# Schemactic_LEDspot.net
KiCad netlist of a schematic drawn in EasyEDA
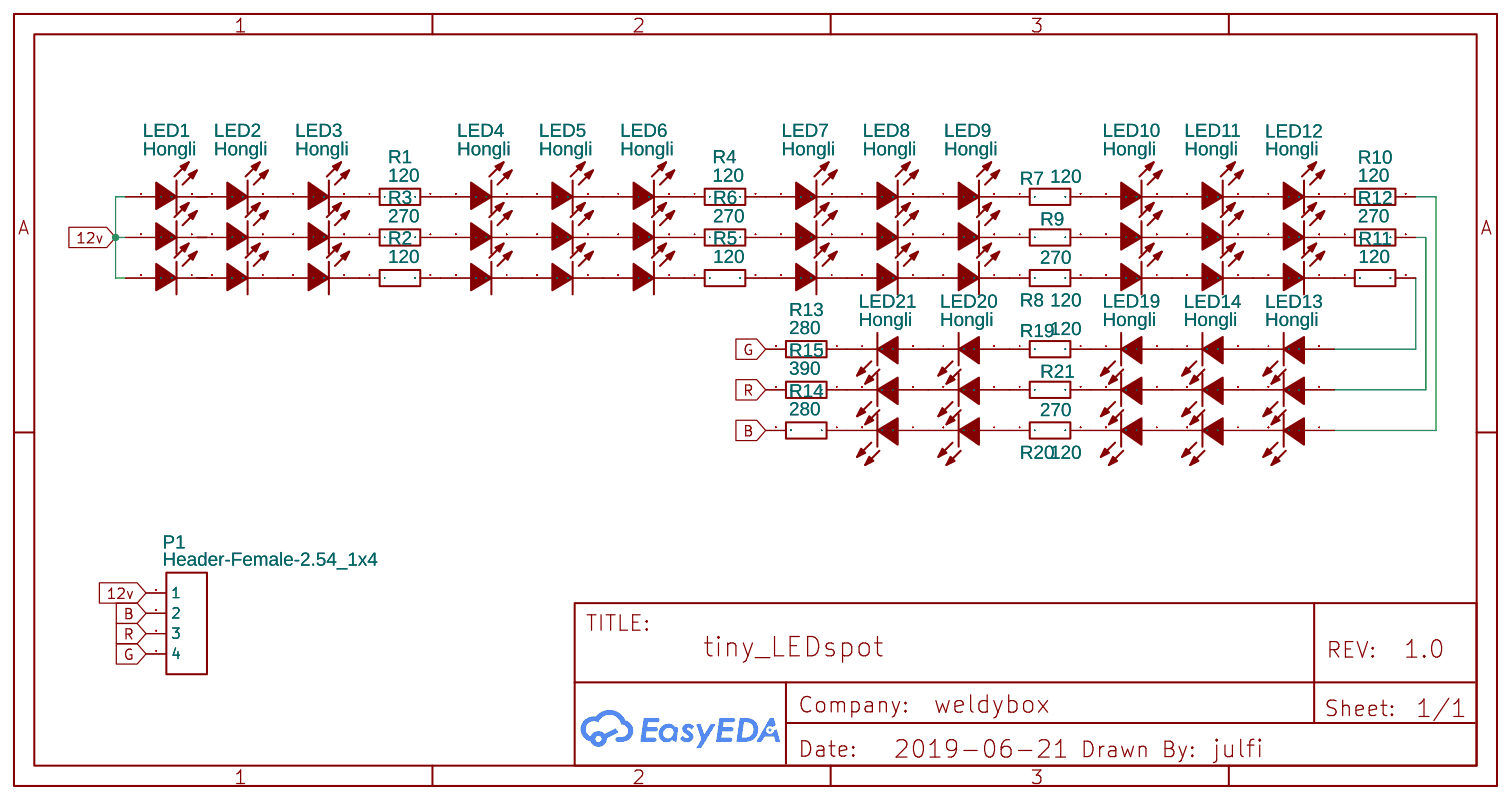
[diagram p0: schematic sheet]

(export (version "E")
  (design (tool "Eeschema 10.0.6"))
  (components
    (comp (ref "LED1")
      (value "Hongli")
      (fields
        (field (name "BOM_Manufacturer Part") "HL-AF-5060H271BU46FU79GC-S1-THL")
        (field (name "BOM_Supplier Part") "C219409")
      )
      (libsource (lib "") (part "Unknown_70_440"))
    )
    (comp (ref "LED2")
      (value "Hongli")
      (fields
        (field (name "BOM_Manufacturer Part") "HL-AF-5060H271BU46FU79GC-S1-THL")
        (field (name "BOM_Supplier Part") "C219409")
      )
      (libsource (lib "") (part "Unknown_105_440"))
    )
    (comp (ref "LED3")
      (value "Hongli")
      (fields
        (field (name "BOM_Manufacturer Part") "HL-AF-5060H271BU46FU79GC-S1-THL")
        (field (name "BOM_Supplier Part") "C219409")
      )
      (libsource (lib "") (part "Unknown_145_440"))
    )
    (comp (ref "LED4")
      (value "Hongli")
      (fields
        (field (name "BOM_Manufacturer Part") "HL-AF-5060H271BU46FU79GC-S1-THL")
        (field (name "BOM_Supplier Part") "C219409")
      )
      (libsource (lib "") (part "Unknown_225_440"))
    )
    (comp (ref "LED5")
      (value "Hongli")
      (fields
        (field (name "BOM_Manufacturer Part") "HL-AF-5060H271BU46FU79GC-S1-THL")
        (field (name "BOM_Supplier Part") "C219409")
      )
      (libsource (lib "") (part "Unknown_265_440"))
    )
    (comp (ref "LED6")
      (value "Hongli")
      (fields
        (field (name "BOM_Manufacturer Part") "HL-AF-5060H271BU46FU79GC-S1-THL")
        (field (name "BOM_Supplier Part") "C219409")
      )
      (libsource (lib "") (part "Unknown_305_440"))
    )
    (comp (ref "LED7")
      (value "Hongli")
      (fields
        (field (name "BOM_Manufacturer Part") "HL-AF-5060H271BU46FU79GC-S1-THL")
        (field (name "BOM_Supplier Part") "C219409")
      )
      (libsource (lib "") (part "Unknown_385_440"))
    )
    (comp (ref "LED8")
      (value "Hongli")
      (fields
        (field (name "BOM_Manufacturer Part") "HL-AF-5060H271BU46FU79GC-S1-THL")
        (field (name "BOM_Supplier Part") "C219409")
      )
      (libsource (lib "") (part "Unknown_425_440"))
    )
    (comp (ref "LED9")
      (value "Hongli")
      (fields
        (field (name "BOM_Manufacturer Part") "HL-AF-5060H271BU46FU79GC-S1-THL")
        (field (name "BOM_Supplier Part") "C219409")
      )
      (libsource (lib "") (part "Unknown_465_440"))
    )
    (comp (ref "LED10")
      (value "Hongli")
      (fields
        (field (name "BOM_Manufacturer Part") "HL-AF-5060H271BU46FU79GC-S1-THL")
        (field (name "BOM_Supplier Part") "C219409")
      )
      (libsource (lib "") (part "Unknown_545_440"))
    )
    (comp (ref "LED11")
      (value "Hongli")
      (fields
        (field (name "BOM_Manufacturer Part") "HL-AF-5060H271BU46FU79GC-S1-THL")
        (field (name "BOM_Supplier Part") "C219409")
      )
      (libsource (lib "") (part "Unknown_585_440"))
    )
    (comp (ref "LED12")
      (value "Hongli")
      (fields
        (field (name "BOM_Manufacturer Part") "HL-AF-5060H271BU46FU79GC-S1-THL")
        (field (name "BOM_Supplier Part") "C219409")
      )
      (libsource (lib "") (part "Unknown_625_440"))
    )
    (comp (ref "LED13")
      (value "Hongli")
      (fields
        (field (name "BOM_Manufacturer Part") "HL-AF-5060H271BU46FU79GC-S1-THL")
        (field (name "BOM_Supplier Part") "C219409")
      )
      (libsource (lib "") (part "Unknown_625_515"))
    )
    (comp (ref "LED14")
      (value "Hongli")
      (fields
        (field (name "BOM_Manufacturer Part") "HL-AF-5060H271BU46FU79GC-S1-THL")
        (field (name "BOM_Supplier Part") "C219409")
      )
      (libsource (lib "") (part "Unknown_585_515"))
    )
    (comp (ref "LED19")
      (value "Hongli")
      (fields
        (field (name "BOM_Manufacturer Part") "HL-AF-5060H271BU46FU79GC-S1-THL")
        (field (name "BOM_Supplier Part") "C219409")
      )
      (libsource (lib "") (part "Unknown_545_515"))
    )
    (comp (ref "LED20")
      (value "Hongli")
      (fields
        (field (name "BOM_Manufacturer Part") "HL-AF-5060H271BU46FU79GC-S1-THL")
        (field (name "BOM_Supplier Part") "C219409")
      )
      (libsource (lib "") (part "Unknown_465_515"))
    )
    (comp (ref "LED21")
      (value "Hongli")
      (fields
        (field (name "BOM_Manufacturer Part") "HL-AF-5060H271BU46FU79GC-S1-THL")
        (field (name "BOM_Supplier Part") "C219409")
      )
      (libsource (lib "") (part "Unknown_425_515"))
    )
    (comp (ref "P1")
      (value "Header-Female-2.54_1x4")
      (fields (field (name "BOM_Supplier Part") "C124413"))
      (libsource (lib "") (part "Unknown_75_630"))
    )
    (comp (ref "R1")
      (value "120")
      (fields
        (field (name "BOM_Manufacturer Part") "0805W8J0121T5E")
        (field (name "BOM_Supplier Part") "C25280")
      )
      (libsource (lib "") (part "0805W8J0121T5E"))
    )
    (comp (ref "R2")
      (value "120")
      (fields
        (field (name "BOM_Manufacturer Part") "0805W8J0121T5E")
        (field (name "BOM_Supplier Part") "C25280")
      )
      (libsource (lib "") (part "0805W8J0121T5E"))
    )
    (comp (ref "R3")
      (value "270")
      (fields
        (field (name "BOM_Manufacturer Part") "RS-05K271JT")
        (field (name "BOM_Supplier Part") "C115004")
      )
      (libsource (lib "") (part "RS-05K271JT"))
    )
    (comp (ref "R4")
      (value "120")
      (fields
        (field (name "BOM_Manufacturer Part") "0805W8J0121T5E")
        (field (name "BOM_Supplier Part") "C25280")
      )
      (libsource (lib "") (part "0805W8J0121T5E"))
    )
    (comp (ref "R5")
      (value "120")
      (fields
        (field (name "BOM_Manufacturer Part") "0805W8J0121T5E")
        (field (name "BOM_Supplier Part") "C25280")
      )
      (libsource (lib "") (part "0805W8J0121T5E"))
    )
    (comp (ref "R6")
      (value "270")
      (fields
        (field (name "BOM_Manufacturer Part") "RS-05K271JT")
        (field (name "BOM_Supplier Part") "C115004")
      )
      (libsource (lib "") (part "RS-05K271JT"))
    )
    (comp (ref "R7")
      (value "120")
      (fields
        (field (name "BOM_Manufacturer Part") "0805W8J0121T5E")
        (field (name "BOM_Supplier Part") "C25280")
      )
      (libsource (lib "") (part "0805W8J0121T5E"))
    )
    (comp (ref "R8")
      (value "120")
      (fields
        (field (name "BOM_Manufacturer Part") "0805W8J0121T5E")
        (field (name "BOM_Supplier Part") "C25280")
      )
      (libsource (lib "") (part "0805W8J0121T5E"))
    )
    (comp (ref "R9")
      (value "270")
      (fields
        (field (name "BOM_Manufacturer Part") "RS-05K271JT")
        (field (name "BOM_Supplier Part") "C115004")
      )
      (libsource (lib "") (part "RS-05K271JT"))
    )
    (comp (ref "R10")
      (value "120")
      (fields
        (field (name "BOM_Manufacturer Part") "0805W8J0121T5E")
        (field (name "BOM_Supplier Part") "C25280")
      )
      (libsource (lib "") (part "0805W8J0121T5E"))
    )
    (comp (ref "R11")
      (value "120")
      (fields
        (field (name "BOM_Manufacturer Part") "0805W8J0121T5E")
        (field (name "BOM_Supplier Part") "C25280")
      )
      (libsource (lib "") (part "0805W8J0121T5E"))
    )
    (comp (ref "R12")
      (value "270")
      (fields
        (field (name "BOM_Manufacturer Part") "RS-05K271JT")
        (field (name "BOM_Supplier Part") "C115004")
      )
      (libsource (lib "") (part "RS-05K271JT"))
    )
    (comp (ref "R13")
      (value "280")
      (fields
        (field (name "BOM_Manufacturer Part") "0805W8F2800T5E")
        (field (name "BOM_Supplier Part") "C247037")
      )
      (libsource (lib "") (part "0805W8F2800T5E"))
    )
    (comp (ref "R14")
      (value "280")
      (fields
        (field (name "BOM_Manufacturer Part") "0805W8F2800T5E")
        (field (name "BOM_Supplier Part") "C247037")
      )
      (libsource (lib "") (part "0805W8F2800T5E"))
    )
    (comp (ref "R15")
      (value "390")
      (fields
        (field (name "BOM_Manufacturer Part") "RTT053900FTP")
        (field (name "BOM_Supplier Part") "C104278")
      )
      (libsource (lib "") (part "RTT053900FTP"))
    )
    (comp (ref "R19")
      (value "120")
      (fields
        (field (name "BOM_Manufacturer Part") "0805W8J0121T5E")
        (field (name "BOM_Supplier Part") "C25280")
      )
      (libsource (lib "") (part "0805W8J0121T5E"))
    )
    (comp (ref "R20")
      (value "120")
      (fields
        (field (name "BOM_Manufacturer Part") "0805W8J0121T5E")
        (field (name "BOM_Supplier Part") "C25280")
      )
      (libsource (lib "") (part "0805W8J0121T5E"))
    )
    (comp (ref "R21")
      (value "270")
      (fields
        (field (name "BOM_Manufacturer Part") "RS-05K271JT")
        (field (name "BOM_Supplier Part") "C115004")
      )
      (libsource (lib "") (part "RS-05K271JT"))
    )
  )
  (nets
    (net (code "1") (name "12v") (class "Default")
      (node (ref "LED1") (pin "1") (pinfunction "A_1") (pintype "unspecified"))
      (node (ref "LED1") (pin "2") (pinfunction "A_2") (pintype "unspecified"))
      (node (ref "LED1") (pin "3") (pinfunction "A_3") (pintype "unspecified"))
      (node (ref "P1") (pin "1") (pinfunction "1_1") (pintype "input"))
    )
    (net (code "2") (name "B") (class "Default")
      (node (ref "P1") (pin "2") (pinfunction "2_2") (pintype "input"))
      (node (ref "R14") (pin "2") (pinfunction "2_2") (pintype "unspecified"))
    )
    (net (code "3") (name "G") (class "Default")
      (node (ref "P1") (pin "4") (pinfunction "4_4") (pintype "input"))
      (node (ref "R13") (pin "2") (pinfunction "2_2") (pintype "unspecified"))
    )
    (net (code "4") (name "Net-(LED1-C-Pad4)") (class "Default")
      (node (ref "LED1") (pin "4") (pinfunction "C_4") (pintype "unspecified"))
      (node (ref "LED2") (pin "3") (pinfunction "A_3") (pintype "unspecified"))
    )
    (net (code "5") (name "Net-(LED1-C-Pad5)") (class "Default")
      (node (ref "LED1") (pin "5") (pinfunction "C_5") (pintype "unspecified"))
      (node (ref "LED2") (pin "2") (pinfunction "A_2") (pintype "unspecified"))
    )
    (net (code "6") (name "Net-(LED1-C-Pad6)") (class "Default")
      (node (ref "LED1") (pin "6") (pinfunction "C_6") (pintype "unspecified"))
      (node (ref "LED2") (pin "1") (pinfunction "A_1") (pintype "unspecified"))
    )
    (net (code "7") (name "Net-(LED2-C-Pad4)") (class "Default")
      (node (ref "LED2") (pin "4") (pinfunction "C_4") (pintype "unspecified"))
      (node (ref "LED3") (pin "3") (pinfunction "A_3") (pintype "unspecified"))
    )
    (net (code "8") (name "Net-(LED2-C-Pad5)") (class "Default")
      (node (ref "LED2") (pin "5") (pinfunction "C_5") (pintype "unspecified"))
      (node (ref "LED3") (pin "2") (pinfunction "A_2") (pintype "unspecified"))
    )
    (net (code "9") (name "Net-(LED2-C-Pad6)") (class "Default")
      (node (ref "LED2") (pin "6") (pinfunction "C_6") (pintype "unspecified"))
      (node (ref "LED3") (pin "1") (pinfunction "A_1") (pintype "unspecified"))
    )
    (net (code "10") (name "Net-(LED3-C-Pad4)") (class "Default")
      (node (ref "LED3") (pin "4") (pinfunction "C_4") (pintype "unspecified"))
      (node (ref "R2") (pin "1") (pinfunction "1_1") (pintype "input"))
    )
    (net (code "11") (name "Net-(LED3-C-Pad5)") (class "Default")
      (node (ref "LED3") (pin "5") (pinfunction "C_5") (pintype "unspecified"))
      (node (ref "R3") (pin "1") (pinfunction "1_1") (pintype "input"))
    )
    (net (code "12") (name "Net-(LED3-C-Pad6)") (class "Default")
      (node (ref "LED3") (pin "6") (pinfunction "C_6") (pintype "unspecified"))
      (node (ref "R1") (pin "1") (pinfunction "1_1") (pintype "input"))
    )
    (net (code "13") (name "Net-(LED4-A-Pad1)") (class "Default")
      (node (ref "LED4") (pin "1") (pinfunction "A_1") (pintype "unspecified"))
      (node (ref "R1") (pin "2") (pinfunction "2_2") (pintype "input"))
    )
    (net (code "14") (name "Net-(LED4-A-Pad2)") (class "Default")
      (node (ref "LED4") (pin "2") (pinfunction "A_2") (pintype "unspecified"))
      (node (ref "R3") (pin "2") (pinfunction "2_2") (pintype "input"))
    )
    (net (code "15") (name "Net-(LED4-A-Pad3)") (class "Default")
      (node (ref "LED4") (pin "3") (pinfunction "A_3") (pintype "unspecified"))
      (node (ref "R2") (pin "2") (pinfunction "2_2") (pintype "input"))
    )
    (net (code "16") (name "Net-(LED4-C-Pad4)") (class "Default")
      (node (ref "LED4") (pin "4") (pinfunction "C_4") (pintype "unspecified"))
      (node (ref "LED5") (pin "3") (pinfunction "A_3") (pintype "unspecified"))
    )
    (net (code "17") (name "Net-(LED4-C-Pad5)") (class "Default")
      (node (ref "LED4") (pin "5") (pinfunction "C_5") (pintype "unspecified"))
      (node (ref "LED5") (pin "2") (pinfunction "A_2") (pintype "unspecified"))
    )
    (net (code "18") (name "Net-(LED4-C-Pad6)") (class "Default")
      (node (ref "LED4") (pin "6") (pinfunction "C_6") (pintype "unspecified"))
      (node (ref "LED5") (pin "1") (pinfunction "A_1") (pintype "unspecified"))
    )
    (net (code "19") (name "Net-(LED5-C-Pad4)") (class "Default")
      (node (ref "LED5") (pin "4") (pinfunction "C_4") (pintype "unspecified"))
      (node (ref "LED6") (pin "3") (pinfunction "A_3") (pintype "unspecified"))
    )
    (net (code "20") (name "Net-(LED5-C-Pad5)") (class "Default")
      (node (ref "LED5") (pin "5") (pinfunction "C_5") (pintype "unspecified"))
      (node (ref "LED6") (pin "2") (pinfunction "A_2") (pintype "unspecified"))
    )
    (net (code "21") (name "Net-(LED5-C-Pad6)") (class "Default")
      (node (ref "LED5") (pin "6") (pinfunction "C_6") (pintype "unspecified"))
      (node (ref "LED6") (pin "1") (pinfunction "A_1") (pintype "unspecified"))
    )
    (net (code "22") (name "Net-(LED6-C-Pad4)") (class "Default")
      (node (ref "LED6") (pin "4") (pinfunction "C_4") (pintype "unspecified"))
      (node (ref "R5") (pin "1") (pinfunction "1_1") (pintype "input"))
    )
    (net (code "23") (name "Net-(LED6-C-Pad5)") (class "Default")
      (node (ref "LED6") (pin "5") (pinfunction "C_5") (pintype "unspecified"))
      (node (ref "R6") (pin "1") (pinfunction "1_1") (pintype "input"))
    )
    (net (code "24") (name "Net-(LED6-C-Pad6)") (class "Default")
      (node (ref "LED6") (pin "6") (pinfunction "C_6") (pintype "unspecified"))
      (node (ref "R4") (pin "1") (pinfunction "1_1") (pintype "input"))
    )
    (net (code "25") (name "Net-(LED7-A-Pad1)") (class "Default")
      (node (ref "LED7") (pin "1") (pinfunction "A_1") (pintype "unspecified"))
      (node (ref "R4") (pin "2") (pinfunction "2_2") (pintype "input"))
    )
    (net (code "26") (name "Net-(LED7-A-Pad2)") (class "Default")
      (node (ref "LED7") (pin "2") (pinfunction "A_2") (pintype "unspecified"))
      (node (ref "R6") (pin "2") (pinfunction "2_2") (pintype "input"))
    )
    (net (code "27") (name "Net-(LED7-A-Pad3)") (class "Default")
      (node (ref "LED7") (pin "3") (pinfunction "A_3") (pintype "unspecified"))
      (node (ref "R5") (pin "2") (pinfunction "2_2") (pintype "input"))
    )
    (net (code "28") (name "Net-(LED7-C-Pad4)") (class "Default")
      (node (ref "LED7") (pin "4") (pinfunction "C_4") (pintype "unspecified"))
      (node (ref "LED8") (pin "3") (pinfunction "A_3") (pintype "unspecified"))
    )
    (net (code "29") (name "Net-(LED7-C-Pad5)") (class "Default")
      (node (ref "LED7") (pin "5") (pinfunction "C_5") (pintype "unspecified"))
      (node (ref "LED8") (pin "2") (pinfunction "A_2") (pintype "unspecified"))
    )
    (net (code "30") (name "Net-(LED7-C-Pad6)") (class "Default")
      (node (ref "LED7") (pin "6") (pinfunction "C_6") (pintype "unspecified"))
      (node (ref "LED8") (pin "1") (pinfunction "A_1") (pintype "unspecified"))
    )
    (net (code "31") (name "Net-(LED8-C-Pad4)") (class "Default")
      (node (ref "LED8") (pin "4") (pinfunction "C_4") (pintype "unspecified"))
      (node (ref "LED9") (pin "3") (pinfunction "A_3") (pintype "unspecified"))
    )
    (net (code "32") (name "Net-(LED8-C-Pad5)") (class "Default")
      (node (ref "LED8") (pin "5") (pinfunction "C_5") (pintype "unspecified"))
      (node (ref "LED9") (pin "2") (pinfunction "A_2") (pintype "unspecified"))
    )
    (net (code "33") (name "Net-(LED8-C-Pad6)") (class "Default")
      (node (ref "LED8") (pin "6") (pinfunction "C_6") (pintype "unspecified"))
      (node (ref "LED9") (pin "1") (pinfunction "A_1") (pintype "unspecified"))
    )
    (net (code "34") (name "Net-(LED9-C-Pad4)") (class "Default")
      (node (ref "LED9") (pin "4") (pinfunction "C_4") (pintype "unspecified"))
      (node (ref "R8") (pin "1") (pinfunction "1_1") (pintype "input"))
    )
    (net (code "35") (name "Net-(LED9-C-Pad5)") (class "Default")
      (node (ref "LED9") (pin "5") (pinfunction "C_5") (pintype "unspecified"))
      (node (ref "R9") (pin "1") (pinfunction "1_1") (pintype "input"))
    )
    (net (code "36") (name "Net-(LED9-C-Pad6)") (class "Default")
      (node (ref "LED9") (pin "6") (pinfunction "C_6") (pintype "unspecified"))
      (node (ref "R7") (pin "1") (pinfunction "1_1") (pintype "input"))
    )
    (net (code "37") (name "Net-(LED10-A-Pad1)") (class "Default")
      (node (ref "LED10") (pin "1") (pinfunction "A_1") (pintype "unspecified"))
      (node (ref "R7") (pin "2") (pinfunction "2_2") (pintype "input"))
    )
    (net (code "38") (name "Net-(LED10-A-Pad2)") (class "Default")
      (node (ref "LED10") (pin "2") (pinfunction "A_2") (pintype "unspecified"))
      (node (ref "R9") (pin "2") (pinfunction "2_2") (pintype "input"))
    )
    (net (code "39") (name "Net-(LED10-A-Pad3)") (class "Default")
      (node (ref "LED10") (pin "3") (pinfunction "A_3") (pintype "unspecified"))
      (node (ref "R8") (pin "2") (pinfunction "2_2") (pintype "input"))
    )
    (net (code "40") (name "Net-(LED10-C-Pad4)") (class "Default")
      (node (ref "LED10") (pin "4") (pinfunction "C_4") (pintype "unspecified"))
      (node (ref "LED11") (pin "3") (pinfunction "A_3") (pintype "unspecified"))
    )
    (net (code "41") (name "Net-(LED10-C-Pad5)") (class "Default")
      (node (ref "LED10") (pin "5") (pinfunction "C_5") (pintype "unspecified"))
      (node (ref "LED11") (pin "2") (pinfunction "A_2") (pintype "unspecified"))
    )
    (net (code "42") (name "Net-(LED10-C-Pad6)") (class "Default")
      (node (ref "LED10") (pin "6") (pinfunction "C_6") (pintype "unspecified"))
      (node (ref "LED11") (pin "1") (pinfunction "A_1") (pintype "unspecified"))
    )
    (net (code "43") (name "Net-(LED11-C-Pad4)") (class "Default")
      (node (ref "LED11") (pin "4") (pinfunction "C_4") (pintype "unspecified"))
      (node (ref "LED12") (pin "3") (pinfunction "A_3") (pintype "unspecified"))
    )
    (net (code "44") (name "Net-(LED11-C-Pad5)") (class "Default")
      (node (ref "LED11") (pin "5") (pinfunction "C_5") (pintype "unspecified"))
      (node (ref "LED12") (pin "2") (pinfunction "A_2") (pintype "unspecified"))
    )
    (net (code "45") (name "Net-(LED11-C-Pad6)") (class "Default")
      (node (ref "LED11") (pin "6") (pinfunction "C_6") (pintype "unspecified"))
      (node (ref "LED12") (pin "1") (pinfunction "A_1") (pintype "unspecified"))
    )
    (net (code "46") (name "Net-(LED12-C-Pad4)") (class "Default")
      (node (ref "LED12") (pin "4") (pinfunction "C_4") (pintype "unspecified"))
      (node (ref "R11") (pin "1") (pinfunction "1_1") (pintype "input"))
    )
    (net (code "47") (name "Net-(LED12-C-Pad5)") (class "Default")
      (node (ref "LED12") (pin "5") (pinfunction "C_5") (pintype "unspecified"))
      (node (ref "R12") (pin "1") (pinfunction "1_1") (pintype "input"))
    )
    (net (code "48") (name "Net-(LED12-C-Pad6)") (class "Default")
      (node (ref "LED12") (pin "6") (pinfunction "C_6") (pintype "unspecified"))
      (node (ref "R10") (pin "1") (pinfunction "1_1") (pintype "input"))
    )
    (net (code "49") (name "Net-(LED13-A-Pad1)") (class "Default")
      (node (ref "LED13") (pin "1") (pinfunction "A_1") (pintype "unspecified"))
      (node (ref "R10") (pin "2") (pinfunction "2_2") (pintype "input"))
    )
    (net (code "50") (name "Net-(LED13-A-Pad2)") (class "Default")
      (node (ref "LED13") (pin "2") (pinfunction "A_2") (pintype "unspecified"))
      (node (ref "R12") (pin "2") (pinfunction "2_2") (pintype "input"))
    )
    (net (code "51") (name "Net-(LED13-A-Pad3)") (class "Default")
      (node (ref "LED13") (pin "3") (pinfunction "A_3") (pintype "unspecified"))
      (node (ref "R11") (pin "2") (pinfunction "2_2") (pintype "input"))
    )
    (net (code "52") (name "Net-(LED13-C-Pad4)") (class "Default")
      (node (ref "LED13") (pin "4") (pinfunction "C_4") (pintype "unspecified"))
      (node (ref "LED14") (pin "3") (pinfunction "A_3") (pintype "unspecified"))
    )
    (net (code "53") (name "Net-(LED13-C-Pad5)") (class "Default")
      (node (ref "LED13") (pin "5") (pinfunction "C_5") (pintype "unspecified"))
      (node (ref "LED14") (pin "2") (pinfunction "A_2") (pintype "unspecified"))
    )
    (net (code "54") (name "Net-(LED13-C-Pad6)") (class "Default")
      (node (ref "LED13") (pin "6") (pinfunction "C_6") (pintype "unspecified"))
      (node (ref "LED14") (pin "1") (pinfunction "A_1") (pintype "unspecified"))
    )
    (net (code "55") (name "Net-(LED14-C-Pad4)") (class "Default")
      (node (ref "LED14") (pin "4") (pinfunction "C_4") (pintype "unspecified"))
      (node (ref "LED19") (pin "3") (pinfunction "A_3") (pintype "unspecified"))
    )
    (net (code "56") (name "Net-(LED14-C-Pad5)") (class "Default")
      (node (ref "LED14") (pin "5") (pinfunction "C_5") (pintype "unspecified"))
      (node (ref "LED19") (pin "2") (pinfunction "A_2") (pintype "unspecified"))
    )
    (net (code "57") (name "Net-(LED14-C-Pad6)") (class "Default")
      (node (ref "LED14") (pin "6") (pinfunction "C_6") (pintype "unspecified"))
      (node (ref "LED19") (pin "1") (pinfunction "A_1") (pintype "unspecified"))
    )
    (net (code "58") (name "Net-(LED19-C-Pad4)") (class "Default")
      (node (ref "LED19") (pin "4") (pinfunction "C_4") (pintype "unspecified"))
      (node (ref "R19") (pin "2") (pinfunction "2_2") (pintype "input"))
    )
    (net (code "59") (name "Net-(LED19-C-Pad5)") (class "Default")
      (node (ref "LED19") (pin "5") (pinfunction "C_5") (pintype "unspecified"))
      (node (ref "R21") (pin "2") (pinfunction "2_2") (pintype "input"))
    )
    (net (code "60") (name "Net-(LED19-C-Pad6)") (class "Default")
      (node (ref "LED19") (pin "6") (pinfunction "C_6") (pintype "unspecified"))
      (node (ref "R20") (pin "2") (pinfunction "2_2") (pintype "input"))
    )
    (net (code "61") (name "Net-(LED20-A-Pad1)") (class "Default")
      (node (ref "LED20") (pin "1") (pinfunction "A_1") (pintype "unspecified"))
      (node (ref "R20") (pin "1") (pinfunction "1_1") (pintype "input"))
    )
    (net (code "62") (name "Net-(LED20-A-Pad2)") (class "Default")
      (node (ref "LED20") (pin "2") (pinfunction "A_2") (pintype "unspecified"))
      (node (ref "R21") (pin "1") (pinfunction "1_1") (pintype "input"))
    )
    (net (code "63") (name "Net-(LED20-A-Pad3)") (class "Default")
      (node (ref "LED20") (pin "3") (pinfunction "A_3") (pintype "unspecified"))
      (node (ref "R19") (pin "1") (pinfunction "1_1") (pintype "input"))
    )
    (net (code "64") (name "Net-(LED20-C-Pad4)") (class "Default")
      (node (ref "LED20") (pin "4") (pinfunction "C_4") (pintype "unspecified"))
      (node (ref "LED21") (pin "3") (pinfunction "A_3") (pintype "unspecified"))
    )
    (net (code "65") (name "Net-(LED20-C-Pad5)") (class "Default")
      (node (ref "LED20") (pin "5") (pinfunction "C_5") (pintype "unspecified"))
      (node (ref "LED21") (pin "2") (pinfunction "A_2") (pintype "unspecified"))
    )
    (net (code "66") (name "Net-(LED20-C-Pad6)") (class "Default")
      (node (ref "LED20") (pin "6") (pinfunction "C_6") (pintype "unspecified"))
      (node (ref "LED21") (pin "1") (pinfunction "A_1") (pintype "unspecified"))
    )
    (net (code "67") (name "Net-(LED21-C-Pad4)") (class "Default")
      (node (ref "LED21") (pin "4") (pinfunction "C_4") (pintype "unspecified"))
      (node (ref "R13") (pin "1") (pinfunction "1_1") (pintype "unspecified"))
    )
    (net (code "68") (name "Net-(LED21-C-Pad5)") (class "Default")
      (node (ref "LED21") (pin "5") (pinfunction "C_5") (pintype "unspecified"))
      (node (ref "R15") (pin "1") (pinfunction "1_1") (pintype "input"))
    )
    (net (code "69") (name "Net-(LED21-C-Pad6)") (class "Default")
      (node (ref "LED21") (pin "6") (pinfunction "C_6") (pintype "unspecified"))
      (node (ref "R14") (pin "1") (pinfunction "1_1") (pintype "unspecified"))
    )
    (net (code "70") (name "R") (class "Default")
      (node (ref "P1") (pin "3") (pinfunction "3_3") (pintype "input"))
      (node (ref "R15") (pin "2") (pinfunction "2_2") (pintype "input"))
    )
  )
)
